# Logic_Unit.net
KiCad netlist of a schematic drawn in Altium Designer
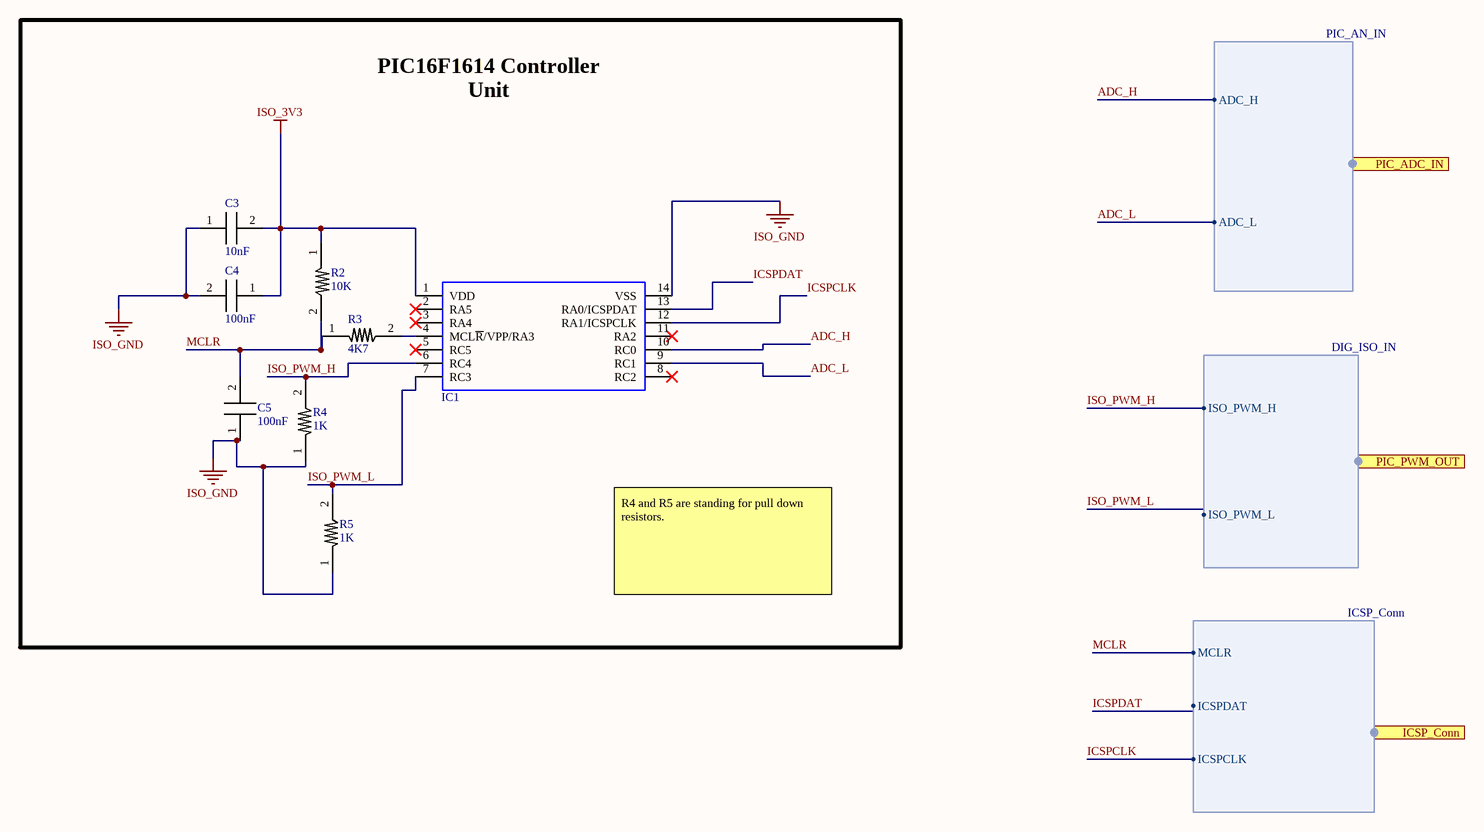
[diagram p0: Logic_Unit.SchDoc]

(export (version "E")
  (design (tool "Eeschema 10.0.6"))
  (components
    (comp (ref "C3")
      (value "CAP 10nF")
      (footprint "0603_CAP")
      (fields (field (name "PARAMETER 1") "10nF"))
      (libsource (lib "Schlib1") (part "CAP 10nF"))
    )
    (comp (ref "C4")
      (value "CAP 100nF")
      (footprint "0603_CAP")
      (fields (field (name "PARAMETER 1") "100nF"))
      (libsource (lib "Schlib1") (part "CAP 100nF"))
    )
    (comp (ref "C5")
      (value "CAP 100nF")
      (footprint "0603_CAP")
      (fields (field (name "PARAMETER 1") "100nF"))
      (libsource (lib "Schlib1") (part "CAP 100nF"))
    )
    (comp (ref "IC1")
      (value "PIC16F1614")
      (footprint "PIC16F1613")
      (libsource (lib "Schlib1") (part "IC PIC16, PIC16F1614"))
    )
    (comp (ref "R2")
      (value "RES, 10K, 0603")
      (footprint "0603_RES")
      (fields (field (name "PARAMETER 1") "10K"))
      (libsource (lib "Schlib1") (part "RES, 10K, 0603"))
    )
    (comp (ref "R3")
      (value "RES, 4K7, 0603")
      (footprint "0603_RES")
      (fields (field (name "PARAMETER 1") "4K7"))
      (libsource (lib "Schlib1") (part "RES, 4K7, 0603"))
    )
    (comp (ref "R4")
      (value "RES, 1K, 0603")
      (footprint "0603_RES")
      (fields (field (name "PARAMETER 1") "1K"))
      (libsource (lib "Schlib1") (part "RES, 1K, 0603"))
    )
    (comp (ref "R5")
      (value "RES, 1K, 0603")
      (footprint "0603_RES")
      (fields (field (name "PARAMETER 1") "1K"))
      (libsource (lib "Schlib1") (part "RES, 1K, 0603"))
    )
  )
  (nets
    (net (code "4") (name "/ADC_H") (class "Default")
      (node (ref "IC1") (pin "10") (pinfunction "RC0_10") (pintype "passive"))
    )
    (net (code "5") (name "/ADC_L") (class "Default")
      (node (ref "IC1") (pin "9") (pinfunction "RC1_9") (pintype "passive"))
    )
    (net (code "6") (name "/ICSPCLK") (class "Default")
      (node (ref "IC1") (pin "12") (pinfunction "RA1/ICSPCLK_12") (pintype "passive"))
    )
    (net (code "7") (name "/ICSPDAT") (class "Default")
      (node (ref "IC1") (pin "13") (pinfunction "RA0/ICSPDAT_13") (pintype "passive"))
    )
    (net (code "8") (name "/ISO_PWM_H") (class "Default")
      (node (ref "IC1") (pin "6") (pinfunction "RC4_6") (pintype "passive"))
      (node (ref "R4") (pin "2") (pinfunction "2_2") (pintype "passive"))
    )
    (net (code "9") (name "/ISO_PWM_L") (class "Default")
      (node (ref "IC1") (pin "7") (pinfunction "RC3_7") (pintype "passive"))
      (node (ref "R5") (pin "2") (pinfunction "2_2") (pintype "passive"))
    )
    (net (code "10") (name "/MCLR") (class "Default")
      (node (ref "C5") (pin "2") (pinfunction "2_2") (pintype "passive"))
      (node (ref "R2") (pin "2") (pinfunction "2_2") (pintype "passive"))
      (node (ref "R3") (pin "1") (pinfunction "1_1") (pintype "passive"))
    )
    (net (code "14") (name "ISO_3V3") (class "Default")
      (node (ref "C3") (pin "2") (pinfunction "2_2") (pintype "passive"))
      (node (ref "C4") (pin "1") (pinfunction "1_1") (pintype "passive"))
      (node (ref "IC1") (pin "1") (pinfunction "VDD_1") (pintype "passive"))
      (node (ref "R2") (pin "1") (pinfunction "1_1") (pintype "passive"))
    )
    (net (code "15") (name "ISO_GND") (class "Default")
      (node (ref "C3") (pin "1") (pinfunction "1_1") (pintype "passive"))
      (node (ref "C4") (pin "2") (pinfunction "2_2") (pintype "passive"))
      (node (ref "C5") (pin "1") (pinfunction "1_1") (pintype "passive"))
      (node (ref "IC1") (pin "14") (pinfunction "VSS_14") (pintype "passive"))
      (node (ref "R4") (pin "1") (pinfunction "1_1") (pintype "passive"))
      (node (ref "R5") (pin "1") (pinfunction "1_1") (pintype "passive"))
    )
    (net (code "16") (name "Net-(IC1-MCL~{R}{slash}VPP{slash}RA3)") (class "Default")
      (node (ref "IC1") (pin "4") (pinfunction "MCL~{R}/VPP/RA3_4") (pintype "passive"))
      (node (ref "R3") (pin "2") (pinfunction "2_2") (pintype "passive"))
    )
    (net (code "17") (name "unconnected-(IC1-RA2-Pad11)") (class "Default")
      (node (ref "IC1") (pin "11") (pinfunction "RA2_11") (pintype "passive+no_connect"))
    )
    (net (code "18") (name "unconnected-(IC1-RA4-Pad3)") (class "Default")
      (node (ref "IC1") (pin "3") (pinfunction "RA4_3") (pintype "passive+no_connect"))
    )
    (net (code "19") (name "unconnected-(IC1-RA5-Pad2)") (class "Default")
      (node (ref "IC1") (pin "2") (pinfunction "RA5_2") (pintype "passive+no_connect"))
    )
    (net (code "20") (name "unconnected-(IC1-RC2-Pad8)") (class "Default")
      (node (ref "IC1") (pin "8") (pinfunction "RC2_8") (pintype "passive+no_connect"))
    )
    (net (code "21") (name "unconnected-(IC1-RC5-Pad5)") (class "Default")
      (node (ref "IC1") (pin "5") (pinfunction "RC5_5") (pintype "passive+no_connect"))
    )
  )
)
